# Motor_Drivers.net
KiCad netlist of a schematic drawn in Altium Designer
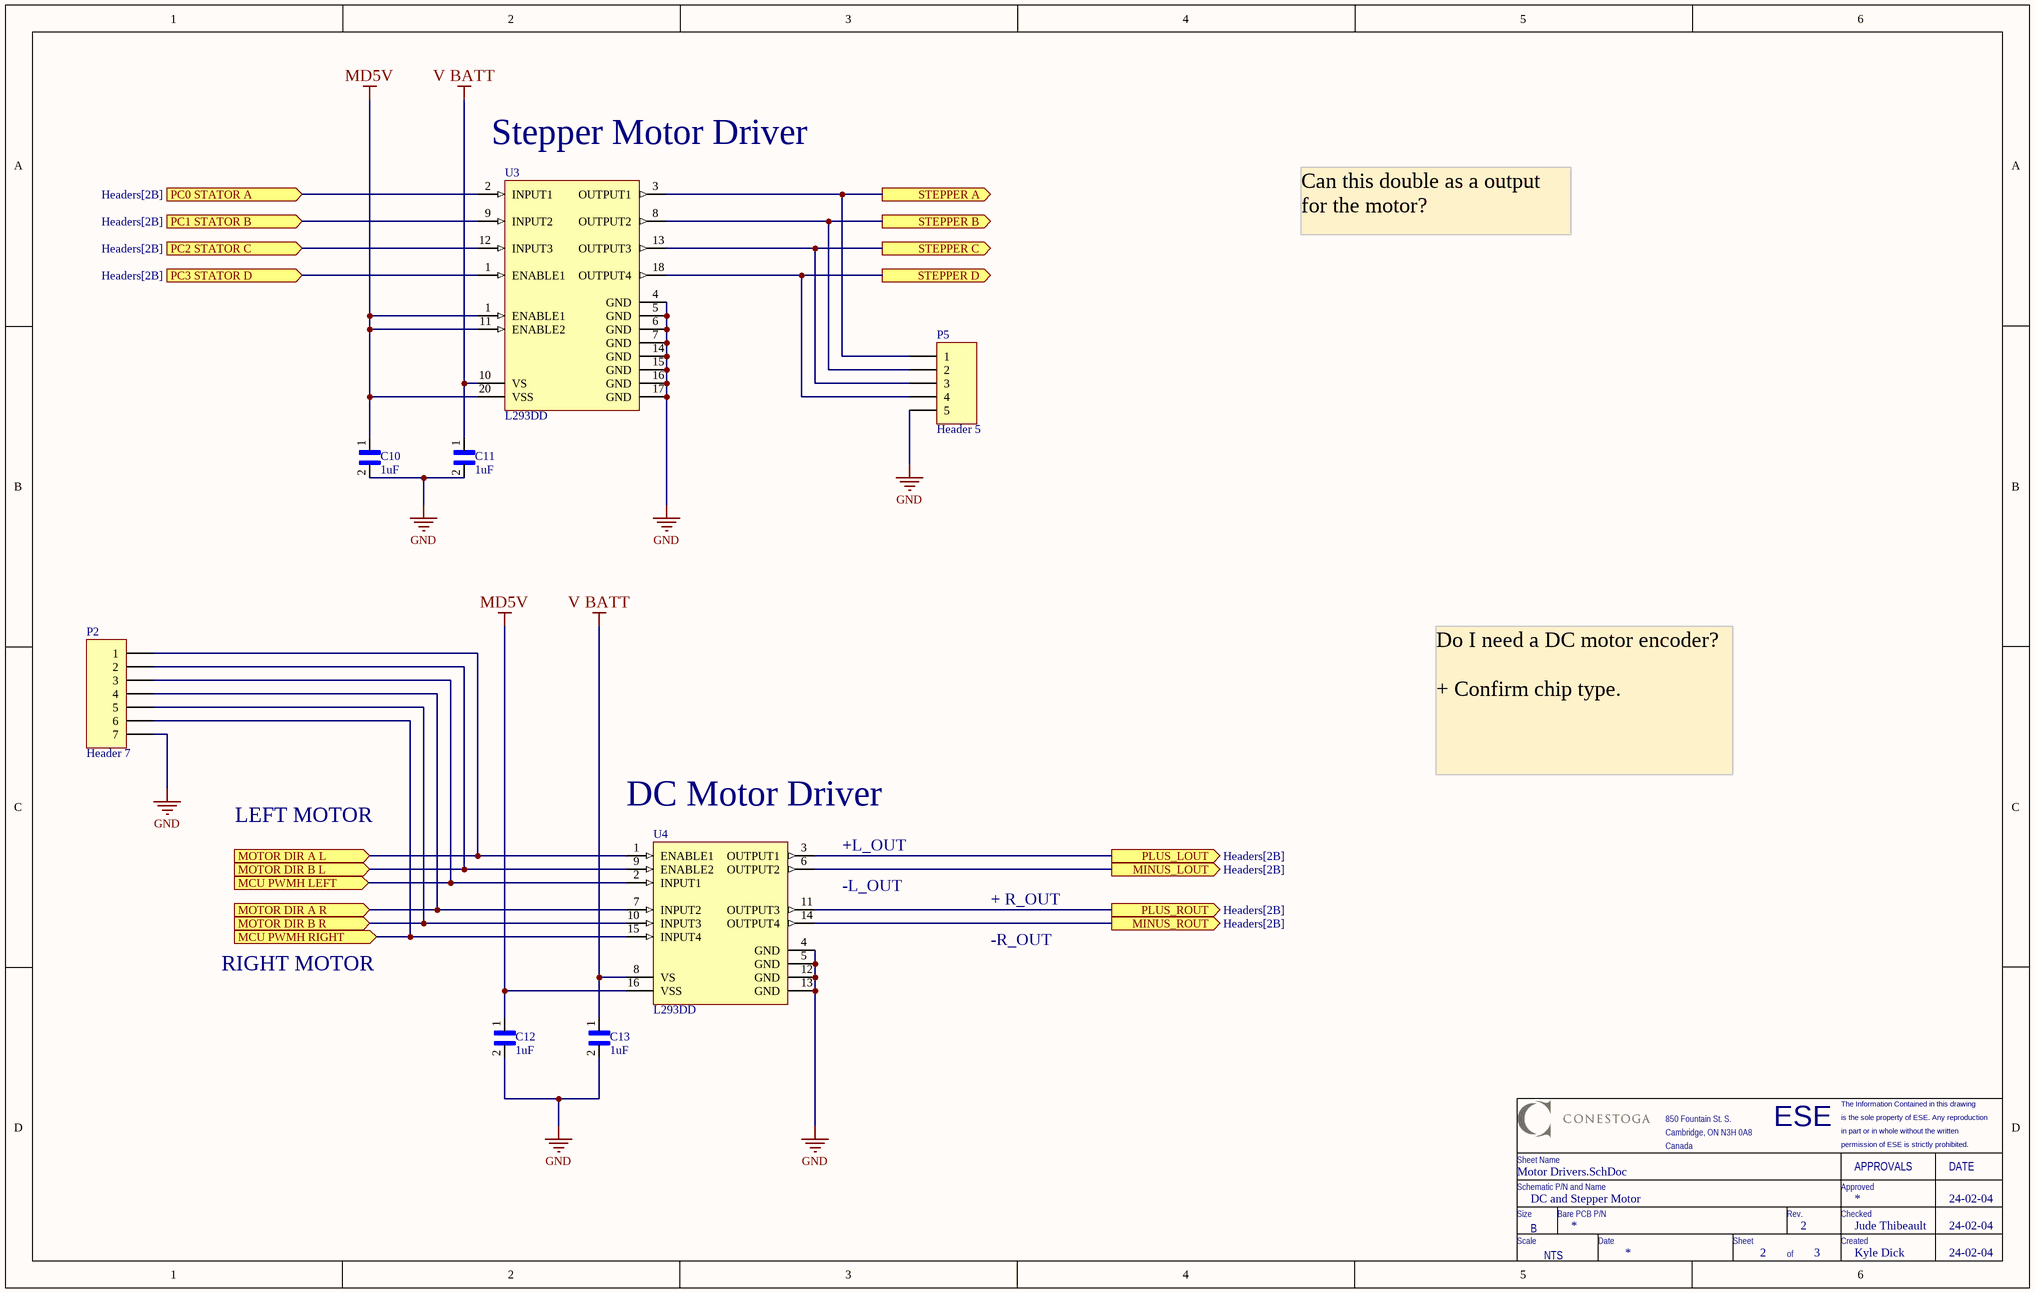
[diagram p0: Motor Drivers.SchDoc]

(export (version "E")
  (design (tool "Eeschema 10.0.6"))
  (components
    (comp (ref "C10")
      (value "1uF")
      (footprint "10 uF Cap")
      (description "Ceramic Capacitor 1210")
      (fields (field (name "MF") "Samsung Electro-Mechanics") (field (name "MP") "CL32A106KBJNNNE"))
      (libsource (lib "PCB1") (part "Capacitor 1uF"))
    )
    (comp (ref "C11")
      (value "1uF")
      (footprint "10 uF Cap")
      (description "Ceramic Capacitor 1210")
      (fields (field (name "MF") "Samsung Electro-Mechanics") (field (name "MP") "CL32A106KBJNNNE"))
      (libsource (lib "PCB1") (part "Capacitor 1uF"))
    )
    (comp (ref "C12")
      (value "1uF")
      (footprint "10 uF Cap")
      (description "Ceramic Capacitor 1210")
      (fields (field (name "MF") "Samsung Electro-Mechanics") (field (name "MP") "CL32A106KBJNNNE"))
      (libsource (lib "PCB1") (part "Capacitor 1uF"))
    )
    (comp (ref "C13")
      (value "1uF")
      (footprint "10 uF Cap")
      (description "Ceramic Capacitor 1210")
      (fields (field (name "MF") "Samsung Electro-Mechanics") (field (name "MP") "CL32A106KBJNNNE"))
      (libsource (lib "PCB1") (part "Capacitor 1uF"))
    )
    (comp (ref "P2")
      (value "Header 7")
      (footprint "HDR1X7")
      (description "Header, 7-Pin Male")
      (fields (field (name "MPN") "PEC07SFAN"))
      (libsource (lib "PCB1") (part "Header 7"))
    )
    (comp (ref "P5")
      (value "Header 5")
      (footprint "HDR1X5")
      (description "Header, 5-Pin Male")
      (fields (field (name "MPN") "PEC05SFAN"))
      (libsource (lib "PCB1") (part "Header 5"))
    )
    (comp (ref "U3")
      (value "L293DD")
      (footprint "STM-SOIC-20_M")
      (description "Push-Pull Four Channel Driver with Diodes, 4.5 to 36 V, 20-Pin SOIC, RoHS, Tube")
      (fields (field (name "TOLERANCE") "1%"))
      (libsource (lib "Altium Content Vault") (part "STM-L293DD-SO-20"))
    )
    (comp (ref "U4")
      (value "L293DD")
      (footprint "STM-L293D-16")
      (description "Push-Pull Four Channel Driver with Diode, 4.5 to 36 V, -40 to 150 degC, 16-Pin PDIP, RoHS, Tube")
      (fields (field (name "PARTNUMBER") "L293D") (field (name "MANUFACTURER") "STMicroelectronics"))
      (libsource (lib "Altium Content Vault") (part "STM-L293D-16"))
    )
  )
  (nets
    (net (code "1") (name "/MCU PWMH LEFT") (class "Default")
      (node (ref "P2") (pin "3") (pinfunction "3_3") (pintype "passive"))
      (node (ref "U4") (pin "2") (pinfunction "INPUT1_2") (pintype "input"))
    )
    (net (code "2") (name "/MCU PWMH RIGHT") (class "Default")
      (node (ref "P2") (pin "6") (pinfunction "6_6") (pintype "passive"))
      (node (ref "U4") (pin "15") (pinfunction "INPUT4_15") (pintype "input"))
    )
    (net (code "3") (name "/MINUS_LOUT") (class "Default")
      (node (ref "U4") (pin "6") (pinfunction "OUTPUT2_6") (pintype "output"))
    )
    (net (code "4") (name "/MINUS_ROUT") (class "Default")
      (node (ref "U4") (pin "14") (pinfunction "OUTPUT4_14") (pintype "output"))
    )
    (net (code "5") (name "/MOTOR DIR A L") (class "Default")
      (node (ref "P2") (pin "1") (pinfunction "1_1") (pintype "passive"))
      (node (ref "U4") (pin "1") (pinfunction "ENABLE1_1") (pintype "input"))
    )
    (net (code "6") (name "/MOTOR DIR A R") (class "Default")
      (node (ref "P2") (pin "4") (pinfunction "4_4") (pintype "passive"))
      (node (ref "U4") (pin "7") (pinfunction "INPUT2_7") (pintype "input"))
    )
    (net (code "7") (name "/MOTOR DIR B L") (class "Default")
      (node (ref "P2") (pin "2") (pinfunction "2_2") (pintype "passive"))
      (node (ref "U4") (pin "9") (pinfunction "ENABLE2_9") (pintype "input"))
    )
    (net (code "8") (name "/MOTOR DIR B R") (class "Default")
      (node (ref "P2") (pin "5") (pinfunction "5_5") (pintype "passive"))
      (node (ref "U4") (pin "10") (pinfunction "INPUT3_10") (pintype "input"))
    )
    (net (code "9") (name "/PC0 STATOR A") (class "Default")
      (node (ref "U3") (pin "2") (pinfunction "INPUT1_2") (pintype "input"))
    )
    (net (code "10") (name "/PC1 STATOR B") (class "Default")
      (node (ref "U3") (pin "9") (pinfunction "INPUT2_9") (pintype "input"))
    )
    (net (code "11") (name "/PC2 STATOR C") (class "Default")
      (node (ref "U3") (pin "12") (pinfunction "INPUT3_12") (pintype "input"))
    )
    (net (code "12") (name "/PC3 STATOR D") (class "Default")
      (node (ref "U3") (pin "1") (pinfunction "ENABLE1_1") (pintype "input"))
    )
    (net (code "13") (name "/PLUS_LOUT") (class "Default")
      (node (ref "U4") (pin "3") (pinfunction "OUTPUT1_3") (pintype "output"))
    )
    (net (code "14") (name "/PLUS_ROUT") (class "Default")
      (node (ref "U4") (pin "11") (pinfunction "OUTPUT3_11") (pintype "output"))
    )
    (net (code "15") (name "/STEPPER A") (class "Default")
      (node (ref "P5") (pin "1") (pinfunction "1_1") (pintype "passive"))
      (node (ref "U3") (pin "3") (pinfunction "OUTPUT1_3") (pintype "output"))
    )
    (net (code "16") (name "/STEPPER B") (class "Default")
      (node (ref "P5") (pin "2") (pinfunction "2_2") (pintype "passive"))
      (node (ref "U3") (pin "8") (pinfunction "OUTPUT2_8") (pintype "output"))
    )
    (net (code "17") (name "/STEPPER C") (class "Default")
      (node (ref "P5") (pin "3") (pinfunction "3_3") (pintype "passive"))
      (node (ref "U3") (pin "13") (pinfunction "OUTPUT3_13") (pintype "output"))
    )
    (net (code "18") (name "/STEPPER D") (class "Default")
      (node (ref "P5") (pin "4") (pinfunction "4_4") (pintype "passive"))
      (node (ref "U3") (pin "18") (pinfunction "OUTPUT4_18") (pintype "output"))
    )
    (net (code "19") (name "GND") (class "Default")
      (node (ref "C10") (pin "2") (pinfunction "2_2") (pintype "passive"))
      (node (ref "C11") (pin "2") (pinfunction "2_2") (pintype "passive"))
      (node (ref "C12") (pin "2") (pinfunction "2_2") (pintype "passive"))
      (node (ref "C13") (pin "2") (pinfunction "2_2") (pintype "passive"))
      (node (ref "P2") (pin "7") (pinfunction "7_7") (pintype "passive"))
      (node (ref "P5") (pin "5") (pinfunction "5_5") (pintype "passive"))
      (node (ref "U3") (pin "14") (pinfunction "GND_14") (pintype "power_in"))
      (node (ref "U3") (pin "15") (pinfunction "GND_15") (pintype "power_in"))
      (node (ref "U3") (pin "16") (pinfunction "GND_16") (pintype "power_in"))
      (node (ref "U3") (pin "17") (pinfunction "GND_17") (pintype "power_in"))
      (node (ref "U3") (pin "4") (pinfunction "GND_4") (pintype "power_in"))
      (node (ref "U3") (pin "5") (pinfunction "GND_5") (pintype "power_in"))
      (node (ref "U3") (pin "6") (pinfunction "GND_6") (pintype "power_in"))
      (node (ref "U3") (pin "7") (pinfunction "GND_7") (pintype "power_in"))
      (node (ref "U4") (pin "12") (pinfunction "GND_12") (pintype "power_in"))
      (node (ref "U4") (pin "13") (pinfunction "GND_13") (pintype "power_in"))
      (node (ref "U4") (pin "4") (pinfunction "GND_4") (pintype "power_in"))
      (node (ref "U4") (pin "5") (pinfunction "GND_5") (pintype "power_in"))
    )
    (net (code "20") (name "MD5V") (class "Default")
      (node (ref "C10") (pin "1") (pinfunction "1_1") (pintype "passive"))
      (node (ref "C12") (pin "1") (pinfunction "1_1") (pintype "passive"))
      (node (ref "U3") (pin "1") (pinfunction "ENABLE1_1") (pintype "input"))
      (node (ref "U3") (pin "11") (pinfunction "ENABLE2_11") (pintype "input"))
      (node (ref "U3") (pin "20") (pinfunction "VSS_20") (pintype "power_in"))
      (node (ref "U4") (pin "16") (pinfunction "VSS_16") (pintype "power_in"))
    )
    (net (code "21") (name "V BATT") (class "Default")
      (node (ref "C11") (pin "1") (pinfunction "1_1") (pintype "passive"))
      (node (ref "C13") (pin "1") (pinfunction "1_1") (pintype "passive"))
      (node (ref "U3") (pin "10") (pinfunction "VS_10") (pintype "power_in"))
      (node (ref "U4") (pin "8") (pinfunction "VS_8") (pintype "power_in"))
    )
  )
)
